# vera-module.net
KiCad netlist of a schematic drawn in EAGLE
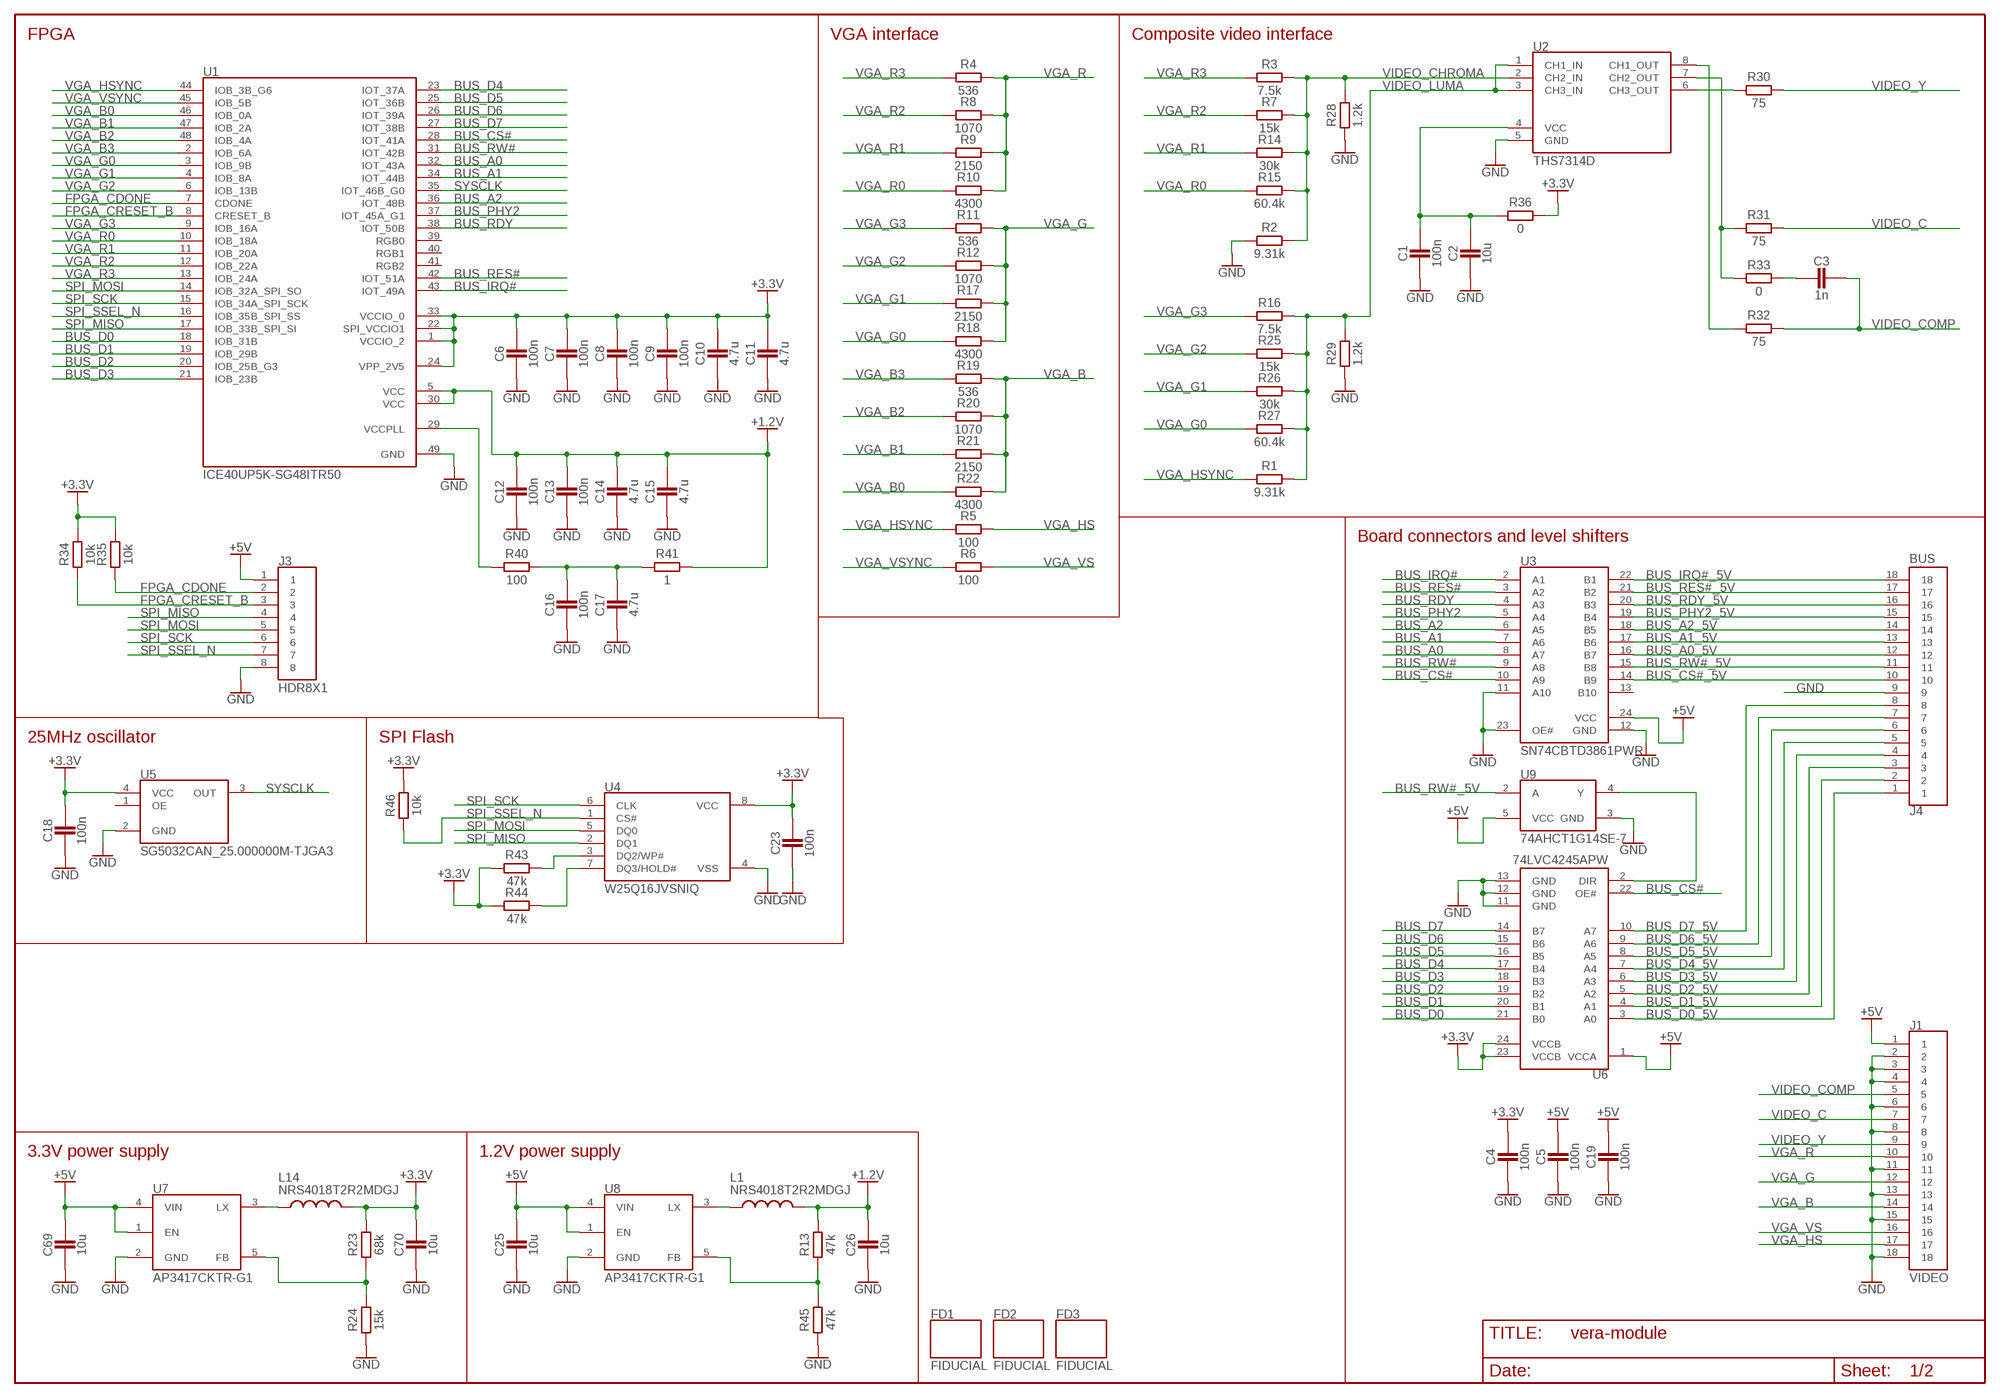
[diagram p0: schematic, sheet 1]
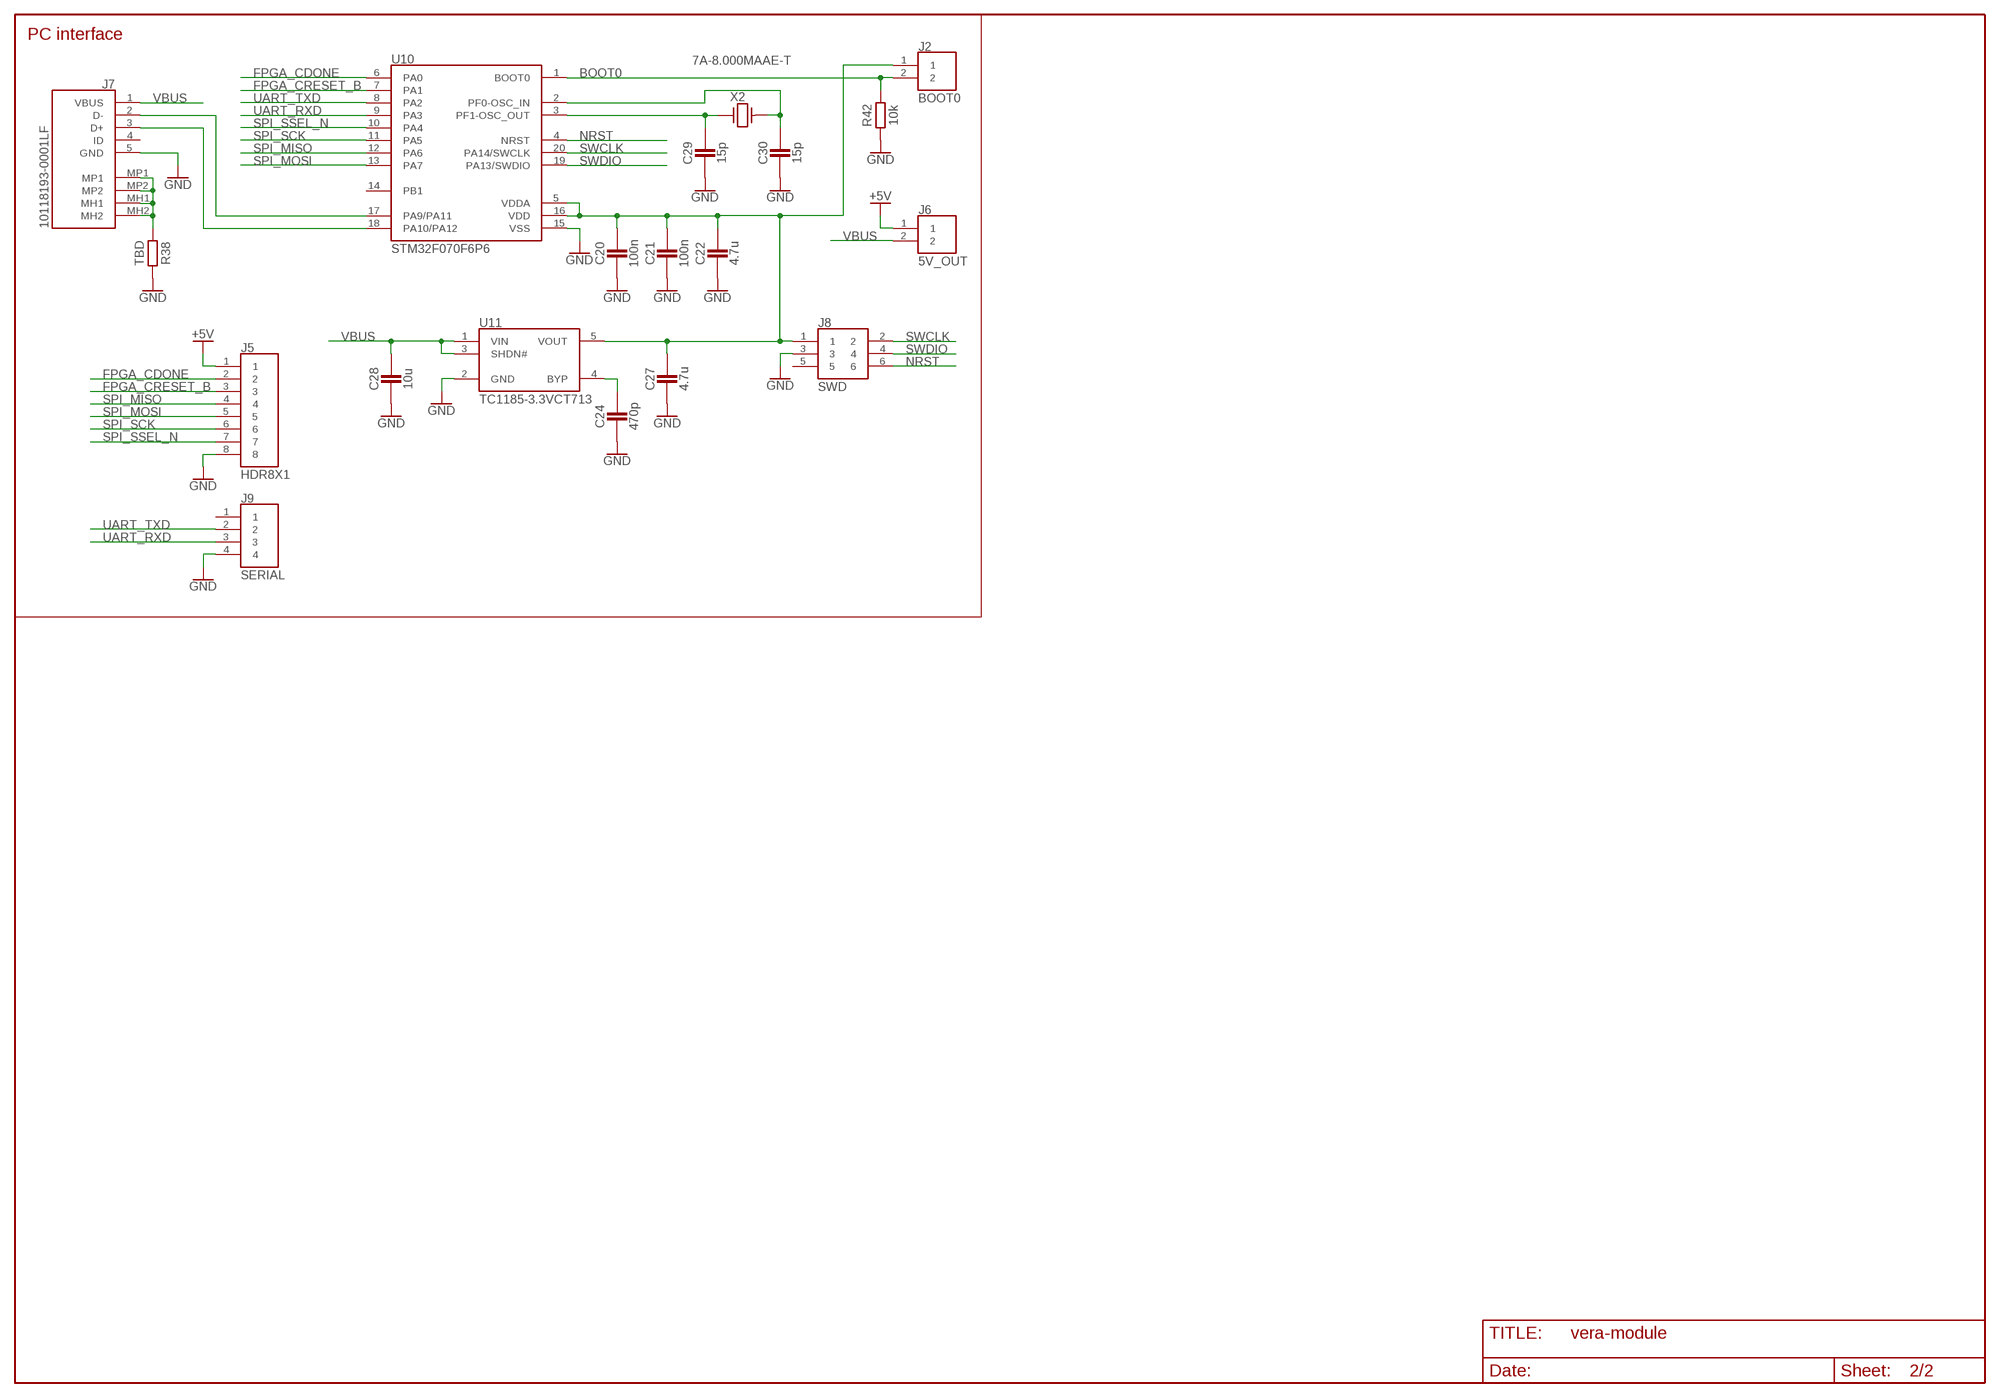
[diagram p1: schematic, sheet 2]

(export (version "E")
  (design (tool "Eeschema 10.0.6"))
  (components
    (comp (ref "C1")
      (value "100n")
      (footprint "eagle-import:C0603")
      (libsource (lib "eagle-import") (part "CAPACITOR0603"))
    )
    (comp (ref "C2")
      (value "10u")
      (footprint "eagle-import:C0805")
      (libsource (lib "eagle-import") (part "CAPACITOR0805"))
    )
    (comp (ref "C3")
      (value "1n")
      (footprint "eagle-import:C0603")
      (libsource (lib "eagle-import") (part "CAPACITOR0603"))
    )
    (comp (ref "C4")
      (value "100n")
      (footprint "eagle-import:C0603")
      (libsource (lib "eagle-import") (part "CAPACITOR0603"))
    )
    (comp (ref "C5")
      (value "100n")
      (footprint "eagle-import:C0603")
      (libsource (lib "eagle-import") (part "CAPACITOR0603"))
    )
    (comp (ref "C6")
      (value "100n")
      (footprint "eagle-import:C0603")
      (libsource (lib "eagle-import") (part "CAPACITOR0603"))
    )
    (comp (ref "C7")
      (value "100n")
      (footprint "eagle-import:C0603")
      (libsource (lib "eagle-import") (part "CAPACITOR0603"))
    )
    (comp (ref "C8")
      (value "100n")
      (footprint "eagle-import:C0603")
      (libsource (lib "eagle-import") (part "CAPACITOR0603"))
    )
    (comp (ref "C9")
      (value "100n")
      (footprint "eagle-import:C0603")
      (libsource (lib "eagle-import") (part "CAPACITOR0603"))
    )
    (comp (ref "C10")
      (value "4.7u")
      (footprint "eagle-import:C0603")
      (libsource (lib "eagle-import") (part "CAPACITOR0603"))
    )
    (comp (ref "C11")
      (value "4.7u")
      (footprint "eagle-import:C0603")
      (libsource (lib "eagle-import") (part "CAPACITOR0603"))
    )
    (comp (ref "C12")
      (value "100n")
      (footprint "eagle-import:C0603")
      (libsource (lib "eagle-import") (part "CAPACITOR0603"))
    )
    (comp (ref "C13")
      (value "100n")
      (footprint "eagle-import:C0603")
      (libsource (lib "eagle-import") (part "CAPACITOR0603"))
    )
    (comp (ref "C14")
      (value "4.7u")
      (footprint "eagle-import:C0603")
      (libsource (lib "eagle-import") (part "CAPACITOR0603"))
    )
    (comp (ref "C15")
      (value "4.7u")
      (footprint "eagle-import:C0603")
      (libsource (lib "eagle-import") (part "CAPACITOR0603"))
    )
    (comp (ref "C16")
      (value "100n")
      (footprint "eagle-import:C0603")
      (libsource (lib "eagle-import") (part "CAPACITOR0603"))
    )
    (comp (ref "C17")
      (value "4.7u")
      (footprint "eagle-import:C0603")
      (libsource (lib "eagle-import") (part "CAPACITOR0603"))
    )
    (comp (ref "C18")
      (value "100n")
      (footprint "eagle-import:C0603")
      (libsource (lib "eagle-import") (part "CAPACITOR0603"))
    )
    (comp (ref "C19")
      (value "100n")
      (footprint "eagle-import:C0603")
      (libsource (lib "eagle-import") (part "CAPACITOR0603"))
    )
    (comp (ref "C23")
      (value "100n")
      (footprint "eagle-import:C0603")
      (libsource (lib "eagle-import") (part "CAPACITOR0603"))
    )
    (comp (ref "C25")
      (value "10u")
      (footprint "eagle-import:C0805")
      (libsource (lib "eagle-import") (part "CAPACITOR0805"))
    )
    (comp (ref "C26")
      (value "10u")
      (footprint "eagle-import:C0805")
      (libsource (lib "eagle-import") (part "CAPACITOR0805"))
    )
    (comp (ref "C69")
      (value "10u")
      (footprint "eagle-import:C0805")
      (libsource (lib "eagle-import") (part "CAPACITOR0805"))
    )
    (comp (ref "C70")
      (value "10u")
      (footprint "eagle-import:C0805")
      (libsource (lib "eagle-import") (part "CAPACITOR0805"))
    )
    (comp (ref "FD1")
      (value "FIDUCIAL")
      (footprint "eagle-import:FIDUCIAL")
      (libsource (lib "eagle-import") (part "FIDUCIAL"))
    )
    (comp (ref "FD2")
      (value "FIDUCIAL")
      (footprint "eagle-import:FIDUCIAL")
      (libsource (lib "eagle-import") (part "FIDUCIAL"))
    )
    (comp (ref "FD3")
      (value "FIDUCIAL")
      (footprint "eagle-import:FIDUCIAL")
      (libsource (lib "eagle-import") (part "FIDUCIAL"))
    )
    (comp (ref "J1")
      (value "VIDEO")
      (footprint "eagle-import:HDR18X1")
      (libsource (lib "eagle-import") (part "HDR18X1"))
    )
    (comp (ref "J3")
      (value "HDR8X1")
      (footprint "eagle-import:HDR8X1")
      (libsource (lib "eagle-import") (part "HDR8X1"))
    )
    (comp (ref "J4")
      (value "BUS")
      (footprint "eagle-import:HDR18X1")
      (libsource (lib "eagle-import") (part "HDR18X1"))
    )
    (comp (ref "L1")
      (value "NRS4018T2R2MDGJ")
      (footprint "eagle-import:NRS4018")
      (libsource (lib "eagle-import") (part "INDUCTORNRS4018"))
    )
    (comp (ref "L14")
      (value "NRS4018T2R2MDGJ")
      (footprint "eagle-import:NRS4018")
      (libsource (lib "eagle-import") (part "INDUCTORNRS4018"))
    )
    (comp (ref "R1")
      (value "9.31k")
      (footprint "eagle-import:R0603")
      (libsource (lib "eagle-import") (part "RESISTOR0603"))
    )
    (comp (ref "R2")
      (value "9.31k")
      (footprint "eagle-import:R0603")
      (libsource (lib "eagle-import") (part "RESISTOR0603"))
    )
    (comp (ref "R3")
      (value "7.5k")
      (footprint "eagle-import:R0603")
      (libsource (lib "eagle-import") (part "RESISTOR0603"))
    )
    (comp (ref "R4")
      (value "536")
      (footprint "eagle-import:R0603")
      (libsource (lib "eagle-import") (part "RESISTOR0603"))
    )
    (comp (ref "R5")
      (value "100")
      (footprint "eagle-import:R0603")
      (libsource (lib "eagle-import") (part "RESISTOR0603"))
    )
    (comp (ref "R6")
      (value "100")
      (footprint "eagle-import:R0603")
      (libsource (lib "eagle-import") (part "RESISTOR0603"))
    )
    (comp (ref "R7")
      (value "15k")
      (footprint "eagle-import:R0603")
      (libsource (lib "eagle-import") (part "RESISTOR0603"))
    )
    (comp (ref "R8")
      (value "1070")
      (footprint "eagle-import:R0603")
      (libsource (lib "eagle-import") (part "RESISTOR0603"))
    )
    (comp (ref "R9")
      (value "2150")
      (footprint "eagle-import:R0603")
      (libsource (lib "eagle-import") (part "RESISTOR0603"))
    )
    (comp (ref "R10")
      (value "4300")
      (footprint "eagle-import:R0603")
      (libsource (lib "eagle-import") (part "RESISTOR0603"))
    )
    (comp (ref "R11")
      (value "536")
      (footprint "eagle-import:R0603")
      (libsource (lib "eagle-import") (part "RESISTOR0603"))
    )
    (comp (ref "R12")
      (value "1070")
      (footprint "eagle-import:R0603")
      (libsource (lib "eagle-import") (part "RESISTOR0603"))
    )
    (comp (ref "R13")
      (value "47k")
      (footprint "eagle-import:R0603")
      (libsource (lib "eagle-import") (part "RESISTOR0603"))
    )
    (comp (ref "R14")
      (value "30k")
      (footprint "eagle-import:R0603")
      (libsource (lib "eagle-import") (part "RESISTOR0603"))
    )
    (comp (ref "R15")
      (value "60.4k")
      (footprint "eagle-import:R0603")
      (libsource (lib "eagle-import") (part "RESISTOR0603"))
    )
    (comp (ref "R16")
      (value "7.5k")
      (footprint "eagle-import:R0603")
      (libsource (lib "eagle-import") (part "RESISTOR0603"))
    )
    (comp (ref "R17")
      (value "2150")
      (footprint "eagle-import:R0603")
      (libsource (lib "eagle-import") (part "RESISTOR0603"))
    )
    (comp (ref "R18")
      (value "4300")
      (footprint "eagle-import:R0603")
      (libsource (lib "eagle-import") (part "RESISTOR0603"))
    )
    (comp (ref "R19")
      (value "536")
      (footprint "eagle-import:R0603")
      (libsource (lib "eagle-import") (part "RESISTOR0603"))
    )
    (comp (ref "R20")
      (value "1070")
      (footprint "eagle-import:R0603")
      (libsource (lib "eagle-import") (part "RESISTOR0603"))
    )
    (comp (ref "R21")
      (value "2150")
      (footprint "eagle-import:R0603")
      (libsource (lib "eagle-import") (part "RESISTOR0603"))
    )
    (comp (ref "R22")
      (value "4300")
      (footprint "eagle-import:R0603")
      (libsource (lib "eagle-import") (part "RESISTOR0603"))
    )
    (comp (ref "R23")
      (value "68k")
      (footprint "eagle-import:R0603")
      (libsource (lib "eagle-import") (part "RESISTOR0603"))
    )
    (comp (ref "R24")
      (value "15k")
      (footprint "eagle-import:R0603")
      (libsource (lib "eagle-import") (part "RESISTOR0603"))
    )
    (comp (ref "R25")
      (value "15k")
      (footprint "eagle-import:R0603")
      (libsource (lib "eagle-import") (part "RESISTOR0603"))
    )
    (comp (ref "R26")
      (value "30k")
      (footprint "eagle-import:R0603")
      (libsource (lib "eagle-import") (part "RESISTOR0603"))
    )
    (comp (ref "R27")
      (value "60.4k")
      (footprint "eagle-import:R0603")
      (libsource (lib "eagle-import") (part "RESISTOR0603"))
    )
    (comp (ref "R28")
      (value "1.2k")
      (footprint "eagle-import:R0603")
      (libsource (lib "eagle-import") (part "RESISTOR0603"))
    )
    (comp (ref "R29")
      (value "1.2k")
      (footprint "eagle-import:R0603")
      (libsource (lib "eagle-import") (part "RESISTOR0603"))
    )
    (comp (ref "R30")
      (value "75")
      (footprint "eagle-import:R0603")
      (libsource (lib "eagle-import") (part "RESISTOR0603"))
    )
    (comp (ref "R31")
      (value "75")
      (footprint "eagle-import:R0603")
      (libsource (lib "eagle-import") (part "RESISTOR0603"))
    )
    (comp (ref "R32")
      (value "75")
      (footprint "eagle-import:R0603")
      (libsource (lib "eagle-import") (part "RESISTOR0603"))
    )
    (comp (ref "R33")
      (value "0")
      (footprint "eagle-import:R0603")
      (libsource (lib "eagle-import") (part "RESISTOR0603"))
    )
    (comp (ref "R34")
      (value "10k")
      (footprint "eagle-import:R0603")
      (libsource (lib "eagle-import") (part "RESISTOR0603"))
    )
    (comp (ref "R35")
      (value "10k")
      (footprint "eagle-import:R0603")
      (libsource (lib "eagle-import") (part "RESISTOR0603"))
    )
    (comp (ref "R36")
      (value "0")
      (footprint "eagle-import:R0603")
      (libsource (lib "eagle-import") (part "RESISTOR0603"))
    )
    (comp (ref "R40")
      (value "100")
      (footprint "eagle-import:R0603")
      (libsource (lib "eagle-import") (part "RESISTOR0603"))
    )
    (comp (ref "R41")
      (value "1")
      (footprint "eagle-import:R0603")
      (libsource (lib "eagle-import") (part "RESISTOR0603"))
    )
    (comp (ref "R43")
      (value "47k")
      (footprint "eagle-import:R0603")
      (libsource (lib "eagle-import") (part "RESISTOR0603"))
    )
    (comp (ref "R44")
      (value "47k")
      (footprint "eagle-import:R0603")
      (libsource (lib "eagle-import") (part "RESISTOR0603"))
    )
    (comp (ref "R45")
      (value "47k")
      (footprint "eagle-import:R0603")
      (libsource (lib "eagle-import") (part "RESISTOR0603"))
    )
    (comp (ref "R46")
      (value "10k")
      (footprint "eagle-import:R0603")
      (libsource (lib "eagle-import") (part "RESISTOR0603"))
    )
    (comp (ref "U1")
      (value "ICE40UP5K-SG48ITR50")
      (footprint "eagle-import:QFN-48")
      (libsource (lib "eagle-import") (part "ICE40UP5K-SG48ITR50"))
    )
    (comp (ref "U2")
      (value "THS7314D")
      (footprint "eagle-import:SOIC-8")
      (libsource (lib "eagle-import") (part "THS7314D"))
    )
    (comp (ref "U3")
      (value "SN74CBTD3861PWR")
      (footprint "eagle-import:TSSOP-24")
      (libsource (lib "eagle-import") (part "SN74CBTD3861PWR"))
    )
    (comp (ref "U4")
      (value "W25Q16JVSNIQ")
      (footprint "eagle-import:SOIC-8")
      (libsource (lib "eagle-import") (part "QSPI_FLASHSOIC8"))
    )
    (comp (ref "U5")
      (value "SG5032CAN_25.000000M-TJGA3")
      (footprint "eagle-import:SG5032")
      (libsource (lib "eagle-import") (part "SG5032CAN_40.000000M-TJGA3"))
    )
    (comp (ref "U6")
      (value "74LVC4245APW")
      (footprint "eagle-import:TSSOP-24")
      (libsource (lib "eagle-import") (part "74LVC4245APW"))
    )
    (comp (ref "U7")
      (value "AP3417CKTR-G1")
      (footprint "eagle-import:SOT-23-5")
      (libsource (lib "eagle-import") (part "AP3417CKTR-G1"))
    )
    (comp (ref "U8")
      (value "AP3417CKTR-G1")
      (footprint "eagle-import:SOT-23-5")
      (libsource (lib "eagle-import") (part "AP3417CKTR-G1"))
    )
    (comp (ref "U9")
      (value "74AHCT1G14SE-7")
      (footprint "eagle-import:TSSOP-5")
      (libsource (lib "eagle-import") (part "74AHCT1G14SE-7"))
    )
    (comp (ref "C20")
      (value "100n")
      (footprint "eagle-import:C0603")
      (libsource (lib "eagle-import") (part "CAPACITOR0603"))
    )
    (comp (ref "C21")
      (value "100n")
      (footprint "eagle-import:C0603")
      (libsource (lib "eagle-import") (part "CAPACITOR0603"))
    )
    (comp (ref "C22")
      (value "4.7u")
      (footprint "eagle-import:C0603")
      (libsource (lib "eagle-import") (part "CAPACITOR0603"))
    )
    (comp (ref "C24")
      (value "470p")
      (footprint "eagle-import:C0603")
      (libsource (lib "eagle-import") (part "CAPACITOR0603"))
    )
    (comp (ref "C27")
      (value "4.7u")
      (footprint "eagle-import:C0603")
      (libsource (lib "eagle-import") (part "CAPACITOR0603"))
    )
    (comp (ref "C28")
      (value "10u")
      (footprint "eagle-import:C0805")
      (libsource (lib "eagle-import") (part "CAPACITOR0805"))
    )
    (comp (ref "C29")
      (value "15p")
      (footprint "eagle-import:C0603")
      (libsource (lib "eagle-import") (part "CAPACITOR0603"))
    )
    (comp (ref "C30")
      (value "15p")
      (footprint "eagle-import:C0603")
      (libsource (lib "eagle-import") (part "CAPACITOR0603"))
    )
    (comp (ref "J2")
      (value "BOOT0")
      (footprint "eagle-import:HDR2X1")
      (libsource (lib "eagle-import") (part "HDR2X1"))
    )
    (comp (ref "J5")
      (value "HDR8X1")
      (footprint "eagle-import:HDR8X1")
      (libsource (lib "eagle-import") (part "HDR8X1"))
    )
    (comp (ref "J6")
      (value "5V_OUT")
      (footprint "eagle-import:HDR2X1")
      (libsource (lib "eagle-import") (part "HDR2X1"))
    )
    (comp (ref "J7")
      (value "10118193-0001LF")
      (footprint "eagle-import:10118193-0001LF")
      (libsource (lib "eagle-import") (part "10118193-0001LF"))
    )
    (comp (ref "J8")
      (value "SWD")
      (footprint "eagle-import:HDR2X3")
      (libsource (lib "eagle-import") (part "HDR2X3"))
    )
    (comp (ref "J9")
      (value "SERIAL")
      (footprint "eagle-import:HDR4X1")
      (libsource (lib "eagle-import") (part "HDR4X1"))
    )
    (comp (ref "R38")
      (value "TBD")
      (footprint "eagle-import:R0603")
      (libsource (lib "eagle-import") (part "RESISTOR0603"))
    )
    (comp (ref "R42")
      (value "10k")
      (footprint "eagle-import:R0603")
      (libsource (lib "eagle-import") (part "RESISTOR0603"))
    )
    (comp (ref "U10")
      (value "STM32F070F6P6")
      (footprint "eagle-import:TSSOP-20")
      (libsource (lib "eagle-import") (part "STM32F070F6P6"))
    )
    (comp (ref "U11")
      (value "TC1185-3.3VCT713")
      (footprint "eagle-import:SOT-23-5")
      (libsource (lib "eagle-import") (part "TC1185-3.3VCT713"))
    )
    (comp (ref "X2")
      (value "7A-8.000MAAE-T")
      (footprint "eagle-import:XTAL2_5X3.2")
      (libsource (lib "eagle-import") (part "XTAL2_5X3.2"))
    )
  )
  (nets
    (net (code "1") (name "+1.2V") (class "Default")
      (node (ref "C12") (pin "2") (pinfunction "2_2") (pintype "passive"))
      (node (ref "C13") (pin "2") (pinfunction "2_2") (pintype "passive"))
      (node (ref "C14") (pin "2") (pinfunction "2_2") (pintype "passive"))
      (node (ref "C15") (pin "2") (pinfunction "2_2") (pintype "passive"))
      (node (ref "C26") (pin "2") (pinfunction "2_2") (pintype "passive"))
      (node (ref "L1") (pin "2") (pinfunction "2_2") (pintype "passive"))
      (node (ref "R13") (pin "2") (pinfunction "2_2") (pintype "passive"))
      (node (ref "R41") (pin "2") (pinfunction "2_2") (pintype "passive"))
      (node (ref "U1") (pin "30") (pinfunction "VCC_30") (pintype "passive"))
      (node (ref "U1") (pin "5") (pinfunction "VCC_5") (pintype "passive"))
    )
    (net (code "2") (name "+3.3V") (class "Default")
      (node (ref "C10") (pin "2") (pinfunction "2_2") (pintype "passive"))
      (node (ref "C11") (pin "2") (pinfunction "2_2") (pintype "passive"))
      (node (ref "C18") (pin "2") (pinfunction "2_2") (pintype "passive"))
      (node (ref "C23") (pin "2") (pinfunction "2_2") (pintype "passive"))
      (node (ref "C4") (pin "2") (pinfunction "2_2") (pintype "passive"))
      (node (ref "C6") (pin "2") (pinfunction "2_2") (pintype "passive"))
      (node (ref "C7") (pin "2") (pinfunction "2_2") (pintype "passive"))
      (node (ref "C70") (pin "2") (pinfunction "2_2") (pintype "passive"))
      (node (ref "C8") (pin "2") (pinfunction "2_2") (pintype "passive"))
      (node (ref "C9") (pin "2") (pinfunction "2_2") (pintype "passive"))
      (node (ref "L14") (pin "2") (pinfunction "2_2") (pintype "passive"))
      (node (ref "R23") (pin "2") (pinfunction "2_2") (pintype "passive"))
      (node (ref "R34") (pin "1") (pinfunction "1_1") (pintype "passive"))
      (node (ref "R35") (pin "1") (pinfunction "1_1") (pintype "passive"))
      (node (ref "R36") (pin "2") (pinfunction "2_2") (pintype "passive"))
      (node (ref "R43") (pin "1") (pinfunction "1_1") (pintype "passive"))
      (node (ref "R44") (pin "1") (pinfunction "1_1") (pintype "passive"))
      (node (ref "R46") (pin "1") (pinfunction "1_1") (pintype "passive"))
      (node (ref "U1") (pin "1") (pinfunction "VCCIO_2_1") (pintype "passive"))
      (node (ref "U1") (pin "22") (pinfunction "SPI_VCCIO1_22") (pintype "passive"))
      (node (ref "U1") (pin "24") (pinfunction "VPP_2V5_24") (pintype "passive"))
      (node (ref "U1") (pin "33") (pinfunction "VCCIO_0_33") (pintype "passive"))
      (node (ref "U4") (pin "8") (pinfunction "VCC_8") (pintype "passive"))
      (node (ref "U5") (pin "4") (pinfunction "VCC_4") (pintype "passive"))
      (node (ref "U6") (pin "23") (pinfunction "VCCB_23") (pintype "passive"))
      (node (ref "U6") (pin "24") (pinfunction "VCCB_24") (pintype "passive"))
    )
    (net (code "3") (name "+5V") (class "Default")
      (node (ref "C19") (pin "2") (pinfunction "2_2") (pintype "passive"))
      (node (ref "C25") (pin "2") (pinfunction "2_2") (pintype "passive"))
      (node (ref "C5") (pin "2") (pinfunction "2_2") (pintype "passive"))
      (node (ref "C69") (pin "2") (pinfunction "2_2") (pintype "passive"))
      (node (ref "J1") (pin "1") (pinfunction "1_1") (pintype "passive"))
      (node (ref "J3") (pin "1") (pinfunction "1_1") (pintype "passive"))
      (node (ref "J5") (pin "1") (pinfunction "1_1") (pintype "passive"))
      (node (ref "J6") (pin "1") (pinfunction "1_1") (pintype "passive"))
      (node (ref "U3") (pin "24") (pinfunction "VCC_24") (pintype "passive"))
      (node (ref "U6") (pin "1") (pinfunction "VCCA_1") (pintype "passive"))
      (node (ref "U7") (pin "1") (pinfunction "EN_1") (pintype "passive"))
      (node (ref "U7") (pin "4") (pinfunction "VIN_4") (pintype "passive"))
      (node (ref "U8") (pin "1") (pinfunction "EN_1") (pintype "passive"))
      (node (ref "U8") (pin "4") (pinfunction "VIN_4") (pintype "passive"))
      (node (ref "U9") (pin "5") (pinfunction "VCC_5") (pintype "passive"))
    )
    (net (code "4") (name "BOOT0") (class "Default")
      (node (ref "J2") (pin "2") (pinfunction "2_2") (pintype "passive"))
      (node (ref "R42") (pin "2") (pinfunction "2_2") (pintype "passive"))
      (node (ref "U10") (pin "1") (pinfunction "BOOT0_1") (pintype "passive"))
    )
    (net (code "5") (name "BUS_A0") (class "Default")
      (node (ref "U1") (pin "32") (pinfunction "IOT_43A_32") (pintype "passive"))
      (node (ref "U3") (pin "8") (pinfunction "A7_8") (pintype "passive"))
    )
    (net (code "6") (name "BUS_A0_5V") (class "Default")
      (node (ref "J4") (pin "12") (pinfunction "12_12") (pintype "passive"))
      (node (ref "U3") (pin "16") (pinfunction "B7_16") (pintype "passive"))
    )
    (net (code "7") (name "BUS_A1") (class "Default")
      (node (ref "U1") (pin "34") (pinfunction "IOT_44B_34") (pintype "passive"))
      (node (ref "U3") (pin "7") (pinfunction "A6_7") (pintype "passive"))
    )
    (net (code "8") (name "BUS_A1_5V") (class "Default")
      (node (ref "J4") (pin "13") (pinfunction "13_13") (pintype "passive"))
      (node (ref "U3") (pin "17") (pinfunction "B6_17") (pintype "passive"))
    )
    (net (code "9") (name "BUS_A2") (class "Default")
      (node (ref "U1") (pin "36") (pinfunction "IOT_48B_36") (pintype "passive"))
      (node (ref "U3") (pin "6") (pinfunction "A5_6") (pintype "passive"))
    )
    (net (code "10") (name "BUS_A2_5V") (class "Default")
      (node (ref "J4") (pin "14") (pinfunction "14_14") (pintype "passive"))
      (node (ref "U3") (pin "18") (pinfunction "B5_18") (pintype "passive"))
    )
    (net (code "11") (name "BUS_CS#") (class "Default")
      (node (ref "U1") (pin "28") (pinfunction "IOT_41A_28") (pintype "passive"))
      (node (ref "U3") (pin "10") (pinfunction "A9_10") (pintype "passive"))
      (node (ref "U6") (pin "22") (pinfunction "OE#_22") (pintype "passive"))
    )
    (net (code "12") (name "BUS_CS#_5V") (class "Default")
      (node (ref "J4") (pin "10") (pinfunction "10_10") (pintype "passive"))
      (node (ref "U3") (pin "14") (pinfunction "B9_14") (pintype "passive"))
    )
    (net (code "13") (name "BUS_D0") (class "Default")
      (node (ref "U1") (pin "18") (pinfunction "IOB_31B_18") (pintype "passive"))
      (node (ref "U6") (pin "21") (pinfunction "B0_21") (pintype "passive"))
    )
    (net (code "14") (name "BUS_D0_5V") (class "Default")
      (node (ref "J4") (pin "1") (pinfunction "1_1") (pintype "passive"))
      (node (ref "U6") (pin "3") (pinfunction "A0_3") (pintype "passive"))
    )
    (net (code "15") (name "BUS_D1") (class "Default")
      (node (ref "U1") (pin "19") (pinfunction "IOB_29B_19") (pintype "passive"))
      (node (ref "U6") (pin "20") (pinfunction "B1_20") (pintype "passive"))
    )
    (net (code "16") (name "BUS_D1_5V") (class "Default")
      (node (ref "J4") (pin "2") (pinfunction "2_2") (pintype "passive"))
      (node (ref "U6") (pin "4") (pinfunction "A1_4") (pintype "passive"))
    )
    (net (code "17") (name "BUS_D2") (class "Default")
      (node (ref "U1") (pin "20") (pinfunction "IOB_25B_G3_20") (pintype "passive"))
      (node (ref "U6") (pin "19") (pinfunction "B2_19") (pintype "passive"))
    )
    (net (code "18") (name "BUS_D2_5V") (class "Default")
      (node (ref "J4") (pin "3") (pinfunction "3_3") (pintype "passive"))
      (node (ref "U6") (pin "5") (pinfunction "A2_5") (pintype "passive"))
    )
    (net (code "19") (name "BUS_D3") (class "Default")
      (node (ref "U1") (pin "21") (pinfunction "IOB_23B_21") (pintype "passive"))
      (node (ref "U6") (pin "18") (pinfunction "B3_18") (pintype "passive"))
    )
    (net (code "20") (name "BUS_D3_5V") (class "Default")
      (node (ref "J4") (pin "4") (pinfunction "4_4") (pintype "passive"))
      (node (ref "U6") (pin "6") (pinfunction "A3_6") (pintype "passive"))
    )
    (net (code "21") (name "BUS_D4") (class "Default")
      (node (ref "U1") (pin "23") (pinfunction "IOT_37A_23") (pintype "passive"))
      (node (ref "U6") (pin "17") (pinfunction "B4_17") (pintype "passive"))
    )
    (net (code "22") (name "BUS_D4_5V") (class "Default")
      (node (ref "J4") (pin "5") (pinfunction "5_5") (pintype "passive"))
      (node (ref "U6") (pin "7") (pinfunction "A4_7") (pintype "passive"))
    )
    (net (code "23") (name "BUS_D5") (class "Default")
      (node (ref "U1") (pin "25") (pinfunction "IOT_36B_25") (pintype "passive"))
      (node (ref "U6") (pin "16") (pinfunction "B5_16") (pintype "passive"))
    )
    (net (code "24") (name "BUS_D5_5V") (class "Default")
      (node (ref "J4") (pin "6") (pinfunction "6_6") (pintype "passive"))
      (node (ref "U6") (pin "8") (pinfunction "A5_8") (pintype "passive"))
    )
    (net (code "25") (name "BUS_D6") (class "Default")
      (node (ref "U1") (pin "26") (pinfunction "IOT_39A_26") (pintype "passive"))
      (node (ref "U6") (pin "15") (pinfunction "B6_15") (pintype "passive"))
    )
    (net (code "26") (name "BUS_D6_5V") (class "Default")
      (node (ref "J4") (pin "7") (pinfunction "7_7") (pintype "passive"))
      (node (ref "U6") (pin "9") (pinfunction "A6_9") (pintype "passive"))
    )
    (net (code "27") (name "BUS_D7") (class "Default")
      (node (ref "U1") (pin "27") (pinfunction "IOT_38B_27") (pintype "passive"))
      (node (ref "U6") (pin "14") (pinfunction "B7_14") (pintype "passive"))
    )
    (net (code "28") (name "BUS_D7_5V") (class "Default")
      (node (ref "J4") (pin "8") (pinfunction "8_8") (pintype "passive"))
      (node (ref "U6") (pin "10") (pinfunction "A7_10") (pintype "passive"))
    )
    (net (code "29") (name "BUS_IRQ#") (class "Default")
      (node (ref "U1") (pin "43") (pinfunction "IOT_49A_43") (pintype "passive"))
      (node (ref "U3") (pin "2") (pinfunction "A1_2") (pintype "passive"))
    )
    (net (code "30") (name "BUS_IRQ#_5V") (class "Default")
      (node (ref "J4") (pin "18") (pinfunction "18_18") (pintype "passive"))
      (node (ref "U3") (pin "22") (pinfunction "B1_22") (pintype "passive"))
    )
    (net (code "31") (name "BUS_PHY2") (class "Default")
      (node (ref "U1") (pin "37") (pinfunction "IOT_45A_G1_37") (pintype "passive"))
      (node (ref "U3") (pin "5") (pinfunction "A4_5") (pintype "passive"))
    )
    (net (code "32") (name "BUS_PHY2_5V") (class "Default")
      (node (ref "J4") (pin "15") (pinfunction "15_15") (pintype "passive"))
      (node (ref "U3") (pin "19") (pinfunction "B4_19") (pintype "passive"))
    )
    (net (code "33") (name "BUS_RDY") (class "Default")
      (node (ref "U1") (pin "38") (pinfunction "IOT_50B_38") (pintype "passive"))
      (node (ref "U3") (pin "4") (pinfunction "A3_4") (pintype "passive"))
    )
    (net (code "34") (name "BUS_RDY_5V") (class "Default")
      (node (ref "J4") (pin "16") (pinfunction "16_16") (pintype "passive"))
      (node (ref "U3") (pin "20") (pinfunction "B3_20") (pintype "passive"))
    )
    (net (code "35") (name "BUS_RES#") (class "Default")
      (node (ref "U1") (pin "42") (pinfunction "IOT_51A_42") (pintype "passive"))
      (node (ref "U3") (pin "3") (pinfunction "A2_3") (pintype "passive"))
    )
    (net (code "36") (name "BUS_RES#_5V") (class "Default")
      (node (ref "J4") (pin "17") (pinfunction "17_17") (pintype "passive"))
      (node (ref "U3") (pin "21") (pinfunction "B2_21") (pintype "passive"))
    )
    (net (code "37") (name "BUS_RW#") (class "Default")
      (node (ref "U1") (pin "31") (pinfunction "IOT_42B_31") (pintype "passive"))
      (node (ref "U3") (pin "9") (pinfunction "A8_9") (pintype "passive"))
    )
    (net (code "38") (name "BUS_RW#_5V") (class "Default")
      (node (ref "J4") (pin "11") (pinfunction "11_11") (pintype "passive"))
      (node (ref "U3") (pin "15") (pinfunction "B8_15") (pintype "passive"))
      (node (ref "U9") (pin "2") (pinfunction "A_2") (pintype "passive"))
    )
    (net (code "39") (name "FPGA_CDONE") (class "Default")
      (node (ref "J3") (pin "2") (pinfunction "2_2") (pintype "passive"))
      (node (ref "J5") (pin "2") (pinfunction "2_2") (pintype "passive"))
      (node (ref "R35") (pin "2") (pinfunction "2_2") (pintype "passive"))
      (node (ref "U1") (pin "7") (pinfunction "CDONE_7") (pintype "passive"))
      (node (ref "U10") (pin "6") (pinfunction "PA0_6") (pintype "passive"))
    )
    (net (code "40") (name "FPGA_CRESET_B") (class "Default")
      (node (ref "J3") (pin "3") (pinfunction "3_3") (pintype "passive"))
      (node (ref "J5") (pin "3") (pinfunction "3_3") (pintype "passive"))
      (node (ref "R34") (pin "2") (pinfunction "2_2") (pintype "passive"))
      (node (ref "U1") (pin "8") (pinfunction "CRESET_B_8") (pintype "passive"))
      (node (ref "U10") (pin "7") (pinfunction "PA1_7") (pintype "passive"))
    )
    (net (code "41") (name "GND") (class "Default")
      (node (ref "C1") (pin "1") (pinfunction "1_1") (pintype "passive"))
      (node (ref "C10") (pin "1") (pinfunction "1_1") (pintype "passive"))
      (node (ref "C11") (pin "1") (pinfunction "1_1") (pintype "passive"))
      (node (ref "C12") (pin "1") (pinfunction "1_1") (pintype "passive"))
      (node (ref "C13") (pin "1") (pinfunction "1_1") (pintype "passive"))
      (node (ref "C14") (pin "1") (pinfunction "1_1") (pintype "passive"))
      (node (ref "C15") (pin "1") (pinfunction "1_1") (pintype "passive"))
      (node (ref "C16") (pin "1") (pinfunction "1_1") (pintype "passive"))
      (node (ref "C17") (pin "1") (pinfunction "1_1") (pintype "passive"))
      (node (ref "C18") (pin "1") (pinfunction "1_1") (pintype "passive"))
      (node (ref "C19") (pin "1") (pinfunction "1_1") (pintype "passive"))
      (node (ref "C2") (pin "1") (pinfunction "1_1") (pintype "passive"))
      (node (ref "C20") (pin "1") (pinfunction "1_1") (pintype "passive"))
      (node (ref "C21") (pin "1") (pinfunction "1_1") (pintype "passive"))
      (node (ref "C22") (pin "1") (pinfunction "1_1") (pintype "passive"))
      (node (ref "C23") (pin "1") (pinfunction "1_1") (pintype "passive"))
      (node (ref "C24") (pin "1") (pinfunction "1_1") (pintype "passive"))
      (node (ref "C25") (pin "1") (pinfunction "1_1") (pintype "passive"))
      (node (ref "C26") (pin "1") (pinfunction "1_1") (pintype "passive"))
      (node (ref "C27") (pin "1") (pinfunction "1_1") (pintype "passive"))
      (node (ref "C28") (pin "1") (pinfunction "1_1") (pintype "passive"))
      (node (ref "C29") (pin "1") (pinfunction "1_1") (pintype "passive"))
      (node (ref "C30") (pin "1") (pinfunction "1_1") (pintype "passive"))
      (node (ref "C4") (pin "1") (pinfunction "1_1") (pintype "passive"))
      (node (ref "C5") (pin "1") (pinfunction "1_1") (pintype "passive"))
      (node (ref "C6") (pin "1") (pinfunction "1_1") (pintype "passive"))
      (node (ref "C69") (pin "1") (pinfunction "1_1") (pintype "passive"))
      (node (ref "C7") (pin "1") (pinfunction "1_1") (pintype "passive"))
      (node (ref "C70") (pin "1") (pinfunction "1_1") (pintype "passive"))
      (node (ref "C8") (pin "1") (pinfunction "1_1") (pintype "passive"))
      (node (ref "C9") (pin "1") (pinfunction "1_1") (pintype "passive"))
      (node (ref "J1") (pin "11") (pinfunction "11_11") (pintype "passive"))
      (node (ref "J1") (pin "13") (pinfunction "13_13") (pintype "passive"))
      (node (ref "J1") (pin "15") (pinfunction "15_15") (pintype "passive"))
      (node (ref "J1") (pin "18") (pinfunction "18_18") (pintype "passive"))
      (node (ref "J1") (pin "2") (pinfunction "2_2") (pintype "passive"))
      (node (ref "J1") (pin "3") (pinfunction "3_3") (pintype "passive"))
      (node (ref "J1") (pin "4") (pinfunction "4_4") (pintype "passive"))
      (node (ref "J1") (pin "6") (pinfunction "6_6") (pintype "passive"))
      (node (ref "J1") (pin "8") (pinfunction "8_8") (pintype "passive"))
      (node (ref "J3") (pin "8") (pinfunction "8_8") (pintype "passive"))
      (node (ref "J4") (pin "9") (pinfunction "9_9") (pintype "passive"))
      (node (ref "J5") (pin "8") (pinfunction "8_8") (pintype "passive"))
      (node (ref "J7") (pin "5") (pinfunction "GND_5") (pintype "passive"))
      (node (ref "J8") (pin "3") (pinfunction "3_3") (pintype "passive"))
      (node (ref "J9") (pin "4") (pinfunction "4_4") (pintype "passive"))
      (node (ref "R2") (pin "1") (pinfunction "1_1") (pintype "passive"))
      (node (ref "R24") (pin "1") (pinfunction "1_1") (pintype "passive"))
      (node (ref "R28") (pin "2") (pinfunction "2_2") (pintype "passive"))
      (node (ref "R29") (pin "2") (pinfunction "2_2") (pintype "passive"))
      (node (ref "R38") (pin "1") (pinfunction "1_1") (pintype "passive"))
      (node (ref "R42") (pin "1") (pinfunction "1_1") (pintype "passive"))
      (node (ref "R45") (pin "1") (pinfunction "1_1") (pintype "passive"))
      (node (ref "U1") (pin "49") (pinfunction "GND_49") (pintype "passive"))
      (node (ref "U10") (pin "15") (pinfunction "VSS_15") (pintype "passive"))
      (node (ref "U11") (pin "2") (pinfunction "GND_2") (pintype "passive"))
      (node (ref "U2") (pin "5") (pinfunction "GND_5") (pintype "passive"))
      (node (ref "U3") (pin "11") (pinfunction "A10_11") (pintype "passive"))
      (node (ref "U3") (pin "12") (pinfunction "GND_12") (pintype "passive"))
      (node (ref "U3") (pin "23") (pinfunction "OE#_23") (pintype "passive"))
      (node (ref "U4") (pin "4") (pinfunction "VSS_4") (pintype "passive"))
      (node (ref "U5") (pin "2") (pinfunction "GND_2") (pintype "passive"))
      (node (ref "U6") (pin "11") (pinfunction "GND_11") (pintype "passive"))
      (node (ref "U6") (pin "12") (pinfunction "GND_12") (pintype "passive"))
      (node (ref "U6") (pin "13") (pinfunction "GND_13") (pintype "passive"))
      (node (ref "U7") (pin "2") (pinfunction "GND_2") (pintype "passive"))
      (node (ref "U8") (pin "2") (pinfunction "GND_2") (pintype "passive"))
      (node (ref "U9") (pin "3") (pinfunction "GND_3") (pintype "passive"))
    )
    (net (code "42") (name "NRST") (class "Default")
      (node (ref "J8") (pin "6") (pinfunction "6_6") (pintype "passive"))
      (node (ref "U10") (pin "4") (pinfunction "NRST_4") (pintype "passive"))
    )
    (net (code "43") (name "Net-(C3-Pad1)") (class "Default")
      (node (ref "C3") (pin "1") (pinfunction "1_1") (pintype "passive"))
      (node (ref "R33") (pin "2") (pinfunction "2_2") (pintype "passive"))
    )
    (net (code "44") (name "Net-(C16-Pad2)") (class "Default")
      (node (ref "C16") (pin "2") (pinfunction "2_2") (pintype "passive"))
      (node (ref "C17") (pin "2") (pinfunction "2_2") (pintype "passive"))
      (node (ref "R40") (pin "2") (pinfunction "2_2") (pintype "passive"))
      (node (ref "R41") (pin "1") (pinfunction "1_1") (pintype "passive"))
    )
    (net (code "45") (name "Net-(J7-D+)") (class "Default")
      (node (ref "J7") (pin "3") (pinfunction "D+_3") (pintype "passive"))
      (node (ref "U10") (pin "18") (pinfunction "PA10/PA12_18") (pintype "passive"))
    )
    (net (code "46") (name "Net-(J7-D-)") (class "Default")
      (node (ref "J7") (pin "2") (pinfunction "D-_2") (pintype "passive"))
      (node (ref "U10") (pin "17") (pinfunction "PA9/PA11_17") (pintype "passive"))
    )
    (net (code "47") (name "Net-(J7-PadMH1)") (class "Default")
      (node (ref "J7") (pin "MH1") (pinfunction "MH1_MH1") (pintype "passive"))
      (node (ref "J7") (pin "MH2") (pinfunction "MH2_MH2") (pintype "passive"))
      (node (ref "J7") (pin "MP1") (pinfunction "MP1_MP1") (pintype "passive"))
      (node (ref "J7") (pin "MP2") (pinfunction "MP2_MP2") (pintype "passive"))
      (node (ref "R38") (pin "2") (pinfunction "2_2") (pintype "passive"))
    )
    (net (code "48") (name "Net-(U1-VCCPLL)") (class "Default")
      (node (ref "R40") (pin "1") (pinfunction "1_1") (pintype "passive"))
      (node (ref "U1") (pin "29") (pinfunction "VCCPLL_29") (pintype "passive"))
    )
    (net (code "49") (name "Net-(U2-CH1_OUT)") (class "Default")
      (node (ref "R32") (pin "1") (pinfunction "1_1") (pintype "passive"))
      (node (ref "U2") (pin "8") (pinfunction "CH1_OUT_8") (pintype "passive"))
    )
    (net (code "50") (name "Net-(U2-CH2_OUT)") (class "Default")
      (node (ref "R31") (pin "1") (pinfunction "1_1") (pintype "passive"))
      (node (ref "R33") (pin "1") (pinfunction "1_1") (pintype "passive"))
      (node (ref "U2") (pin "7") (pinfunction "CH2_OUT_7") (pintype "passive"))
    )
    (net (code "51") (name "Net-(U2-CH3_OUT)") (class "Default")
      (node (ref "R30") (pin "1") (pinfunction "1_1") (pintype "passive"))
      (node (ref "U2") (pin "6") (pinfunction "CH3_OUT_6") (pintype "passive"))
    )
    (net (code "52") (name "Net-(U2-VCC)") (class "Default")
      (node (ref "C1") (pin "2") (pinfunction "2_2") (pintype "passive"))
      (node (ref "C2") (pin "2") (pinfunction "2_2") (pintype "passive"))
      (node (ref "R36") (pin "1") (pinfunction "1_1") (pintype "passive"))
      (node (ref "U2") (pin "4") (pinfunction "VCC_4") (pintype "passive"))
    )
    (net (code "53") (name "Net-(U4-DQ2{slash}WP#)") (class "Default")
      (node (ref "R43") (pin "2") (pinfunction "2_2") (pintype "passive"))
      (node (ref "U4") (pin "3") (pinfunction "DQ2/WP#_3") (pintype "passive"))
    )
    (net (code "54") (name "Net-(U4-DQ3{slash}HOLD#)") (class "Default")
      (node (ref "R44") (pin "2") (pinfunction "2_2") (pintype "passive"))
      (node (ref "U4") (pin "7") (pinfunction "DQ3/HOLD#_7") (pintype "passive"))
    )
    (net (code "55") (name "Net-(U6-DIR)") (class "Default")
      (node (ref "U6") (pin "2") (pinfunction "DIR_2") (pintype "passive"))
      (node (ref "U9") (pin "4") (pinfunction "Y_4") (pintype "passive"))
    )
    (net (code "56") (name "Net-(U7-FB)") (class "Default")
      (node (ref "R23") (pin "1") (pinfunction "1_1") (pintype "passive"))
      (node (ref "R24") (pin "2") (pinfunction "2_2") (pintype "passive"))
      (node (ref "U7") (pin "5") (pinfunction "FB_5") (pintype "passive"))
    )
    (net (code "57") (name "Net-(U7-LX)") (class "Default")
      (node (ref "L14") (pin "1") (pinfunction "1_1") (pintype "passive"))
      (node (ref "U7") (pin "3") (pinfunction "LX_3") (pintype "passive"))
    )
    (net (code "58") (name "Net-(U8-FB)") (class "Default")
      (node (ref "R13") (pin "1") (pinfunction "1_1") (pintype "passive"))
      (node (ref "R45") (pin "2") (pinfunction "2_2") (pintype "passive"))
      (node (ref "U8") (pin "5") (pinfunction "FB_5") (pintype "passive"))
    )
    (net (code "59") (name "Net-(U8-LX)") (class "Default")
      (node (ref "L1") (pin "1") (pinfunction "1_1") (pintype "passive"))
      (node (ref "U8") (pin "3") (pinfunction "LX_3") (pintype "passive"))
    )
    (net (code "60") (name "Net-(U10-PF0-OSC_IN)") (class "Default")
      (node (ref "C30") (pin "2") (pinfunction "2_2") (pintype "passive"))
      (node (ref "U10") (pin "2") (pinfunction "PF0-OSC_IN_2") (pintype "passive"))
      (node (ref "X2") (pin "2") (pinfunction "2_2") (pintype "passive"))
    )
    (net (code "61") (name "Net-(U10-PF1-OSC_OUT)") (class "Default")
      (node (ref "C29") (pin "2") (pinfunction "2_2") (pintype "passive"))
      (node (ref "U10") (pin "3") (pinfunction "PF1-OSC_OUT_3") (pintype "passive"))
      (node (ref "X2") (pin "1") (pinfunction "1_1") (pintype "passive"))
    )
    (net (code "62") (name "Net-(U10-VDD)") (class "Default")
      (node (ref "C20") (pin "2") (pinfunction "2_2") (pintype "passive"))
      (node (ref "C21") (pin "2") (pinfunction "2_2") (pintype "passive"))
      (node (ref "C22") (pin "2") (pinfunction "2_2") (pintype "passive"))
      (node (ref "C27") (pin "2") (pinfunction "2_2") (pintype "passive"))
      (node (ref "J2") (pin "1") (pinfunction "1_1") (pintype "passive"))
      (node (ref "J8") (pin "1") (pinfunction "1_1") (pintype "passive"))
      (node (ref "U10") (pin "16") (pinfunction "VDD_16") (pintype "passive"))
      (node (ref "U10") (pin "5") (pinfunction "VDDA_5") (pintype "passive"))
      (node (ref "U11") (pin "5") (pinfunction "VOUT_5") (pintype "passive"))
    )
    (net (code "63") (name "Net-(U11-BYP)") (class "Default")
      (node (ref "C24") (pin "2") (pinfunction "2_2") (pintype "passive"))
      (node (ref "U11") (pin "4") (pinfunction "BYP_4") (pintype "passive"))
    )
    (net (code "64") (name "SPI_MISO") (class "Default")
      (node (ref "J3") (pin "4") (pinfunction "4_4") (pintype "passive"))
      (node (ref "J5") (pin "4") (pinfunction "4_4") (pintype "passive"))
      (node (ref "U1") (pin "17") (pinfunction "IOB_33B_SPI_SI_17") (pintype "passive"))
      (node (ref "U10") (pin "12") (pinfunction "PA6_12") (pintype "passive"))
      (node (ref "U4") (pin "2") (pinfunction "DQ1_2") (pintype "passive"))
    )
    (net (code "65") (name "SPI_MOSI") (class "Default")
      (node (ref "J3") (pin "5") (pinfunction "5_5") (pintype "passive"))
      (node (ref "J5") (pin "5") (pinfunction "5_5") (pintype "passive"))
      (node (ref "U1") (pin "14") (pinfunction "IOB_32A_SPI_SO_14") (pintype "passive"))
      (node (ref "U10") (pin "13") (pinfunction "PA7_13") (pintype "passive"))
      (node (ref "U4") (pin "5") (pinfunction "DQ0_5") (pintype "passive"))
    )
    (net (code "66") (name "SPI_SCK") (class "Default")
      (node (ref "J3") (pin "6") (pinfunction "6_6") (pintype "passive"))
      (node (ref "J5") (pin "6") (pinfunction "6_6") (pintype "passive"))
      (node (ref "U1") (pin "15") (pinfunction "IOB_34A_SPI_SCK_15") (pintype "passive"))
      (node (ref "U10") (pin "11") (pinfunction "PA5_11") (pintype "passive"))
      (node (ref "U4") (pin "6") (pinfunction "CLK_6") (pintype "passive"))
    )
    (net (code "67") (name "SPI_SSEL_N") (class "Default")
      (node (ref "J3") (pin "7") (pinfunction "7_7") (pintype "passive"))
      (node (ref "J5") (pin "7") (pinfunction "7_7") (pintype "passive"))
      (node (ref "R46") (pin "2") (pinfunction "2_2") (pintype "passive"))
      (node (ref "U1") (pin "16") (pinfunction "IOB_35B_SPI_SS_16") (pintype "passive"))
      (node (ref "U10") (pin "10") (pinfunction "PA4_10") (pintype "passive"))
      (node (ref "U4") (pin "1") (pinfunction "CS#_1") (pintype "passive"))
    )
    (net (code "68") (name "SWCLK") (class "Default")
      (node (ref "J8") (pin "2") (pinfunction "2_2") (pintype "passive"))
      (node (ref "U10") (pin "20") (pinfunction "PA14/SWCLK_20") (pintype "passive"))
    )
    (net (code "69") (name "SWDIO") (class "Default")
      (node (ref "J8") (pin "4") (pinfunction "4_4") (pintype "passive"))
      (node (ref "U10") (pin "19") (pinfunction "PA13/SWDIO_19") (pintype "passive"))
    )
    (net (code "70") (name "SYSCLK") (class "Default")
      (node (ref "U1") (pin "35") (pinfunction "IOT_46B_G0_35") (pintype "passive"))
      (node (ref "U5") (pin "3") (pinfunction "OUT_3") (pintype "passive"))
    )
    (net (code "71") (name "UART_RXD") (class "Default")
      (node (ref "J9") (pin "3") (pinfunction "3_3") (pintype "passive"))
      (node (ref "U10") (pin "9") (pinfunction "PA3_9") (pintype "passive"))
    )
    (net (code "72") (name "UART_TXD") (class "Default")
      (node (ref "J9") (pin "2") (pinfunction "2_2") (pintype "passive"))
      (node (ref "U10") (pin "8") (pinfunction "PA2_8") (pintype "passive"))
    )
    (net (code "73") (name "VBUS") (class "Default")
      (node (ref "C28") (pin "2") (pinfunction "2_2") (pintype "passive"))
      (node (ref "J6") (pin "2") (pinfunction "2_2") (pintype "passive"))
      (node (ref "J7") (pin "1") (pinfunction "VBUS_1") (pintype "passive"))
      (node (ref "U11") (pin "1") (pinfunction "VIN_1") (pintype "passive"))
      (node (ref "U11") (pin "3") (pinfunction "SHDN#_3") (pintype "passive"))
    )
    (net (code "74") (name "VGA_B") (class "Default")
      (node (ref "J1") (pin "14") (pinfunction "14_14") (pintype "passive"))
      (node (ref "R19") (pin "2") (pinfunction "2_2") (pintype "passive"))
      (node (ref "R20") (pin "2") (pinfunction "2_2") (pintype "passive"))
      (node (ref "R21") (pin "2") (pinfunction "2_2") (pintype "passive"))
      (node (ref "R22") (pin "2") (pinfunction "2_2") (pintype "passive"))
    )
    (net (code "75") (name "VGA_B0") (class "Default")
      (node (ref "R22") (pin "1") (pinfunction "1_1") (pintype "passive"))
      (node (ref "U1") (pin "46") (pinfunction "IOB_0A_46") (pintype "passive"))
    )
    (net (code "76") (name "VGA_B1") (class "Default")
      (node (ref "R21") (pin "1") (pinfunction "1_1") (pintype "passive"))
      (node (ref "U1") (pin "47") (pinfunction "IOB_2A_47") (pintype "passive"))
    )
    (net (code "77") (name "VGA_B2") (class "Default")
      (node (ref "R20") (pin "1") (pinfunction "1_1") (pintype "passive"))
      (node (ref "U1") (pin "48") (pinfunction "IOB_4A_48") (pintype "passive"))
    )
    (net (code "78") (name "VGA_B3") (class "Default")
      (node (ref "R19") (pin "1") (pinfunction "1_1") (pintype "passive"))
      (node (ref "U1") (pin "2") (pinfunction "IOB_6A_2") (pintype "passive"))
    )
    (net (code "79") (name "VGA_G") (class "Default")
      (node (ref "J1") (pin "12") (pinfunction "12_12") (pintype "passive"))
      (node (ref "R11") (pin "2") (pinfunction "2_2") (pintype "passive"))
      (node (ref "R12") (pin "2") (pinfunction "2_2") (pintype "passive"))
      (node (ref "R17") (pin "2") (pinfunction "2_2") (pintype "passive"))
      (node (ref "R18") (pin "2") (pinfunction "2_2") (pintype "passive"))
    )
    (net (code "80") (name "VGA_G0") (class "Default")
      (node (ref "R18") (pin "1") (pinfunction "1_1") (pintype "passive"))
      (node (ref "R27") (pin "1") (pinfunction "1_1") (pintype "passive"))
      (node (ref "U1") (pin "3") (pinfunction "IOB_9B_3") (pintype "passive"))
    )
    (net (code "81") (name "VGA_G1") (class "Default")
      (node (ref "R17") (pin "1") (pinfunction "1_1") (pintype "passive"))
      (node (ref "R26") (pin "1") (pinfunction "1_1") (pintype "passive"))
      (node (ref "U1") (pin "4") (pinfunction "IOB_8A_4") (pintype "passive"))
    )
    (net (code "82") (name "VGA_G2") (class "Default")
      (node (ref "R12") (pin "1") (pinfunction "1_1") (pintype "passive"))
      (node (ref "R25") (pin "1") (pinfunction "1_1") (pintype "passive"))
      (node (ref "U1") (pin "6") (pinfunction "IOB_13B_6") (pintype "passive"))
    )
    (net (code "83") (name "VGA_G3") (class "Default")
      (node (ref "R11") (pin "1") (pinfunction "1_1") (pintype "passive"))
      (node (ref "R16") (pin "1") (pinfunction "1_1") (pintype "passive"))
      (node (ref "U1") (pin "9") (pinfunction "IOB_16A_9") (pintype "passive"))
    )
    (net (code "84") (name "VGA_HS") (class "Default")
      (node (ref "J1") (pin "17") (pinfunction "17_17") (pintype "passive"))
      (node (ref "R5") (pin "2") (pinfunction "2_2") (pintype "passive"))
    )
    (net (code "85") (name "VGA_HSYNC") (class "Default")
      (node (ref "R1") (pin "1") (pinfunction "1_1") (pintype "passive"))
      (node (ref "R5") (pin "1") (pinfunction "1_1") (pintype "passive"))
      (node (ref "U1") (pin "44") (pinfunction "IOB_3B_G6_44") (pintype "passive"))
    )
    (net (code "86") (name "VGA_R") (class "Default")
      (node (ref "J1") (pin "10") (pinfunction "10_10") (pintype "passive"))
      (node (ref "R10") (pin "2") (pinfunction "2_2") (pintype "passive"))
      (node (ref "R4") (pin "2") (pinfunction "2_2") (pintype "passive"))
      (node (ref "R8") (pin "2") (pinfunction "2_2") (pintype "passive"))
      (node (ref "R9") (pin "2") (pinfunction "2_2") (pintype "passive"))
    )
    (net (code "87") (name "VGA_R0") (class "Default")
      (node (ref "R10") (pin "1") (pinfunction "1_1") (pintype "passive"))
      (node (ref "R15") (pin "1") (pinfunction "1_1") (pintype "passive"))
      (node (ref "U1") (pin "10") (pinfunction "IOB_18A_10") (pintype "passive"))
    )
    (net (code "88") (name "VGA_R1") (class "Default")
      (node (ref "R14") (pin "1") (pinfunction "1_1") (pintype "passive"))
      (node (ref "R9") (pin "1") (pinfunction "1_1") (pintype "passive"))
      (node (ref "U1") (pin "11") (pinfunction "IOB_20A_11") (pintype "passive"))
    )
    (net (code "89") (name "VGA_R2") (class "Default")
      (node (ref "R7") (pin "1") (pinfunction "1_1") (pintype "passive"))
      (node (ref "R8") (pin "1") (pinfunction "1_1") (pintype "passive"))
      (node (ref "U1") (pin "12") (pinfunction "IOB_22A_12") (pintype "passive"))
    )
    (net (code "90") (name "VGA_R3") (class "Default")
      (node (ref "R3") (pin "1") (pinfunction "1_1") (pintype "passive"))
      (node (ref "R4") (pin "1") (pinfunction "1_1") (pintype "passive"))
      (node (ref "U1") (pin "13") (pinfunction "IOB_24A_13") (pintype "passive"))
    )
    (net (code "91") (name "VGA_VS") (class "Default")
      (node (ref "J1") (pin "16") (pinfunction "16_16") (pintype "passive"))
      (node (ref "R6") (pin "2") (pinfunction "2_2") (pintype "passive"))
    )
    (net (code "92") (name "VGA_VSYNC") (class "Default")
      (node (ref "R6") (pin "1") (pinfunction "1_1") (pintype "passive"))
      (node (ref "U1") (pin "45") (pinfunction "IOB_5B_45") (pintype "passive"))
    )
    (net (code "93") (name "VIDEO_C") (class "Default")
      (node (ref "J1") (pin "7") (pinfunction "7_7") (pintype "passive"))
      (node (ref "R31") (pin "2") (pinfunction "2_2") (pintype "passive"))
    )
    (net (code "94") (name "VIDEO_CHROMA") (class "Default")
      (node (ref "R14") (pin "2") (pinfunction "2_2") (pintype "passive"))
      (node (ref "R15") (pin "2") (pinfunction "2_2") (pintype "passive"))
      (node (ref "R2") (pin "2") (pinfunction "2_2") (pintype "passive"))
      (node (ref "R28") (pin "1") (pinfunction "1_1") (pintype "passive"))
      (node (ref "R3") (pin "2") (pinfunction "2_2") (pintype "passive"))
      (node (ref "R7") (pin "2") (pinfunction "2_2") (pintype "passive"))
      (node (ref "U2") (pin "2") (pinfunction "CH2_IN_2") (pintype "passive"))
    )
    (net (code "95") (name "VIDEO_COMP") (class "Default")
      (node (ref "C3") (pin "2") (pinfunction "2_2") (pintype "passive"))
      (node (ref "J1") (pin "5") (pinfunction "5_5") (pintype "passive"))
      (node (ref "R32") (pin "2") (pinfunction "2_2") (pintype "passive"))
    )
    (net (code "96") (name "VIDEO_LUMA") (class "Default")
      (node (ref "R1") (pin "2") (pinfunction "2_2") (pintype "passive"))
      (node (ref "R16") (pin "2") (pinfunction "2_2") (pintype "passive"))
      (node (ref "R25") (pin "2") (pinfunction "2_2") (pintype "passive"))
      (node (ref "R26") (pin "2") (pinfunction "2_2") (pintype "passive"))
      (node (ref "R27") (pin "2") (pinfunction "2_2") (pintype "passive"))
      (node (ref "R29") (pin "1") (pinfunction "1_1") (pintype "passive"))
      (node (ref "U2") (pin "1") (pinfunction "CH1_IN_1") (pintype "passive"))
      (node (ref "U2") (pin "3") (pinfunction "CH3_IN_3") (pintype "passive"))
    )
    (net (code "97") (name "VIDEO_Y") (class "Default")
      (node (ref "J1") (pin "9") (pinfunction "9_9") (pintype "passive"))
      (node (ref "R30") (pin "2") (pinfunction "2_2") (pintype "passive"))
    )
    (net (code "98") (name "unconnected-(J7-ID-Pad4)") (class "Default")
      (node (ref "J7") (pin "4") (pinfunction "ID_4") (pintype "passive"))
    )
    (net (code "99") (name "unconnected-(J8-Pad5)") (class "Default")
      (node (ref "J8") (pin "5") (pinfunction "5_5") (pintype "passive"))
    )
    (net (code "100") (name "unconnected-(J9-Pad1)") (class "Default")
      (node (ref "J9") (pin "1") (pinfunction "1_1") (pintype "passive"))
    )
    (net (code "101") (name "unconnected-(U1-RGB0-Pad39)") (class "Default")
      (node (ref "U1") (pin "39") (pinfunction "RGB0_39") (pintype "passive"))
    )
    (net (code "102") (name "unconnected-(U1-RGB1-Pad40)") (class "Default")
      (node (ref "U1") (pin "40") (pinfunction "RGB1_40") (pintype "passive"))
    )
    (net (code "103") (name "unconnected-(U1-RGB2-Pad41)") (class "Default")
      (node (ref "U1") (pin "41") (pinfunction "RGB2_41") (pintype "passive"))
    )
    (net (code "104") (name "unconnected-(U3-B10-Pad13)") (class "Default")
      (node (ref "U3") (pin "13") (pinfunction "B10_13") (pintype "passive"))
    )
    (net (code "105") (name "unconnected-(U5-OE-Pad1)") (class "Default")
      (node (ref "U5") (pin "1") (pinfunction "OE_1") (pintype "passive"))
    )
    (net (code "106") (name "unconnected-(U10-PB1-Pad14)") (class "Default")
      (node (ref "U10") (pin "14") (pinfunction "PB1_14") (pintype "passive"))
    )
  )
)
